# LM4811_Audio_Amp.net
KiCad netlist of a schematic drawn in EAGLE
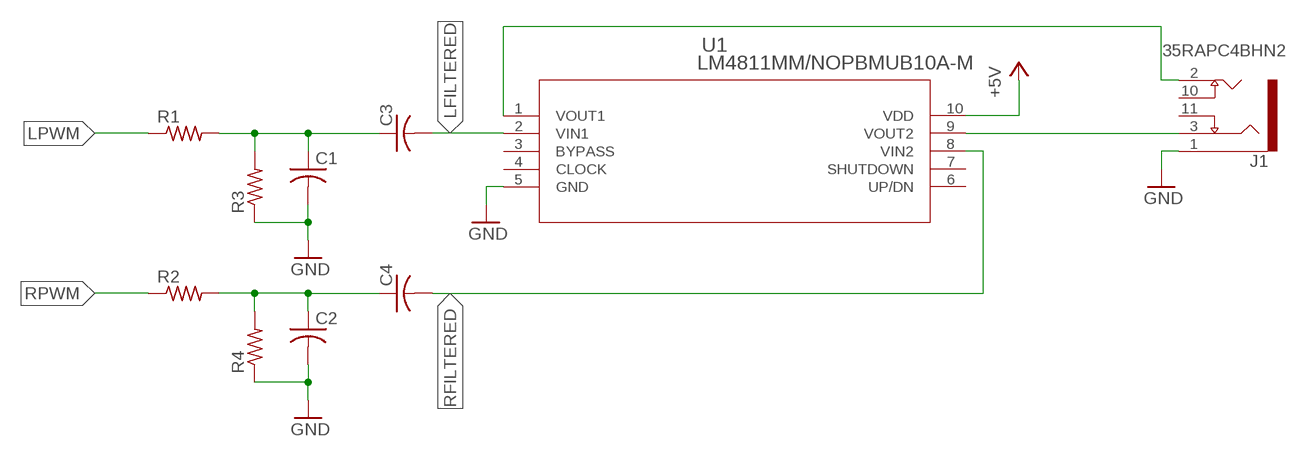
[diagram p0: schematic, sheet 1]

(export (version "E")
  (design (tool "Eeschema 10.0.6"))
  (components
    (comp (ref "C1")
      (value "C-USC0805K")
      (footprint "eagle-import:C0805K")
      (libsource (lib "eagle-import") (part "C-USC0805K"))
    )
    (comp (ref "C2")
      (value "C-USC0805K")
      (footprint "eagle-import:C0805K")
      (libsource (lib "eagle-import") (part "C-USC0805K"))
    )
    (comp (ref "C3")
      (value "C-USC0805K")
      (footprint "eagle-import:C0805K")
      (libsource (lib "eagle-import") (part "C-USC0805K"))
    )
    (comp (ref "C4")
      (value "C-USC0805K")
      (footprint "eagle-import:C0805K")
      (libsource (lib "eagle-import") (part "C-USC0805K"))
    )
    (comp (ref "J1")
      (value "35RAPC4BHN2")
      (footprint "eagle-import:SWITCHCRAFT_35RAPC4BHN2")
      (fields (field (name "DIGI-KEY_PART_NUMBER") "SC1459-ND") (field (name "MF") "Switchcraft"))
      (libsource (lib "eagle-import") (part "35RAPC4BHN2"))
    )
    (comp (ref "R1")
      (value "R-US_R0805")
      (footprint "eagle-import:R0805")
      (libsource (lib "eagle-import") (part "R-US_R0805"))
    )
    (comp (ref "R2")
      (value "R-US_R0805")
      (footprint "eagle-import:R0805")
      (libsource (lib "eagle-import") (part "R-US_R0805"))
    )
    (comp (ref "R3")
      (value "R-US_R0805")
      (footprint "eagle-import:R0805")
      (libsource (lib "eagle-import") (part "R-US_R0805"))
    )
    (comp (ref "R4")
      (value "R-US_R0805")
      (footprint "eagle-import:R0805")
      (libsource (lib "eagle-import") (part "R-US_R0805"))
    )
    (comp (ref "U1")
      (value "LM4811MM/NOPBMUB10A-M")
      (footprint "eagle-import:MUB10A-M")
      (fields (field (name "MANUFACTURER_PART_NUMBER") "LM4811MMNOPB"))
      (libsource (lib "eagle-import") (part "LM4811MM/NOPBMUB10A-M"))
    )
  )
  (nets
    (net (code "1") (name "+5V") (class "Default")
      (node (ref "U1") (pin "10") (pinfunction "VDD_10") (pintype "passive"))
    )
    (net (code "2") (name "GND") (class "Default")
      (node (ref "C1") (pin "2") (pinfunction "2_2") (pintype "passive"))
      (node (ref "C2") (pin "2") (pinfunction "2_2") (pintype "passive"))
      (node (ref "J1") (pin "1") (pinfunction "1_1") (pintype "passive"))
      (node (ref "R3") (pin "1") (pinfunction "1_1") (pintype "passive"))
      (node (ref "R4") (pin "1") (pinfunction "1_1") (pintype "passive"))
      (node (ref "U1") (pin "5") (pinfunction "GND_5") (pintype "passive"))
    )
    (net (code "3") (name "LFILTERED") (class "Default")
      (node (ref "C3") (pin "2") (pinfunction "2_2") (pintype "passive"))
      (node (ref "U1") (pin "2") (pinfunction "VIN1_2") (pintype "input"))
    )
    (net (code "4") (name "LPWM") (class "Default")
      (node (ref "R1") (pin "1") (pinfunction "1_1") (pintype "passive"))
    )
    (net (code "5") (name "Net-(C1-Pad1)") (class "Default")
      (node (ref "C1") (pin "1") (pinfunction "1_1") (pintype "passive"))
      (node (ref "C3") (pin "1") (pinfunction "1_1") (pintype "passive"))
      (node (ref "R1") (pin "2") (pinfunction "2_2") (pintype "passive"))
      (node (ref "R3") (pin "2") (pinfunction "2_2") (pintype "passive"))
    )
    (net (code "6") (name "Net-(C2-Pad1)") (class "Default")
      (node (ref "C2") (pin "1") (pinfunction "1_1") (pintype "passive"))
      (node (ref "C4") (pin "1") (pinfunction "1_1") (pintype "passive"))
      (node (ref "R2") (pin "2") (pinfunction "2_2") (pintype "passive"))
      (node (ref "R4") (pin "2") (pinfunction "2_2") (pintype "passive"))
    )
    (net (code "7") (name "Net-(U1-VOUT1)") (class "Default")
      (node (ref "J1") (pin "2") (pinfunction "2_2") (pintype "passive"))
      (node (ref "U1") (pin "1") (pinfunction "VOUT1_1") (pintype "output"))
    )
    (net (code "8") (name "Net-(U1-VOUT2)") (class "Default")
      (node (ref "J1") (pin "3") (pinfunction "3_3") (pintype "passive"))
      (node (ref "U1") (pin "9") (pinfunction "VOUT2_9") (pintype "output"))
    )
    (net (code "9") (name "RFILTERED") (class "Default")
      (node (ref "C4") (pin "2") (pinfunction "2_2") (pintype "passive"))
      (node (ref "U1") (pin "8") (pinfunction "VIN2_8") (pintype "input"))
    )
    (net (code "10") (name "RPWM") (class "Default")
      (node (ref "R2") (pin "1") (pinfunction "1_1") (pintype "passive"))
    )
    (net (code "11") (name "unconnected-(J1-Pad10)") (class "Default")
      (node (ref "J1") (pin "10") (pinfunction "10_10") (pintype "passive"))
    )
    (net (code "12") (name "unconnected-(J1-Pad11)") (class "Default")
      (node (ref "J1") (pin "11") (pinfunction "11_11") (pintype "passive"))
    )
    (net (code "13") (name "unconnected-(U1-BYPASS-Pad3)") (class "Default")
      (node (ref "U1") (pin "3") (pinfunction "BYPASS_3") (pintype "passive"))
    )
    (net (code "14") (name "unconnected-(U1-CLOCK-Pad4)") (class "Default")
      (node (ref "U1") (pin "4") (pinfunction "CLOCK_4") (pintype "passive"))
    )
    (net (code "15") (name "unconnected-(U1-SHUTDOWN-Pad7)") (class "Default")
      (node (ref "U1") (pin "7") (pinfunction "SHUTDOWN_7") (pintype "passive"))
    )
    (net (code "16") (name "unconnected-(U1-UP{slash}DN-Pad6)") (class "Default")
      (node (ref "U1") (pin "6") (pinfunction "UP/DN_6") (pintype "passive"))
    )
  )
)
